# SimonSays.net
KiCad netlist of a schematic drawn in Altium Designer
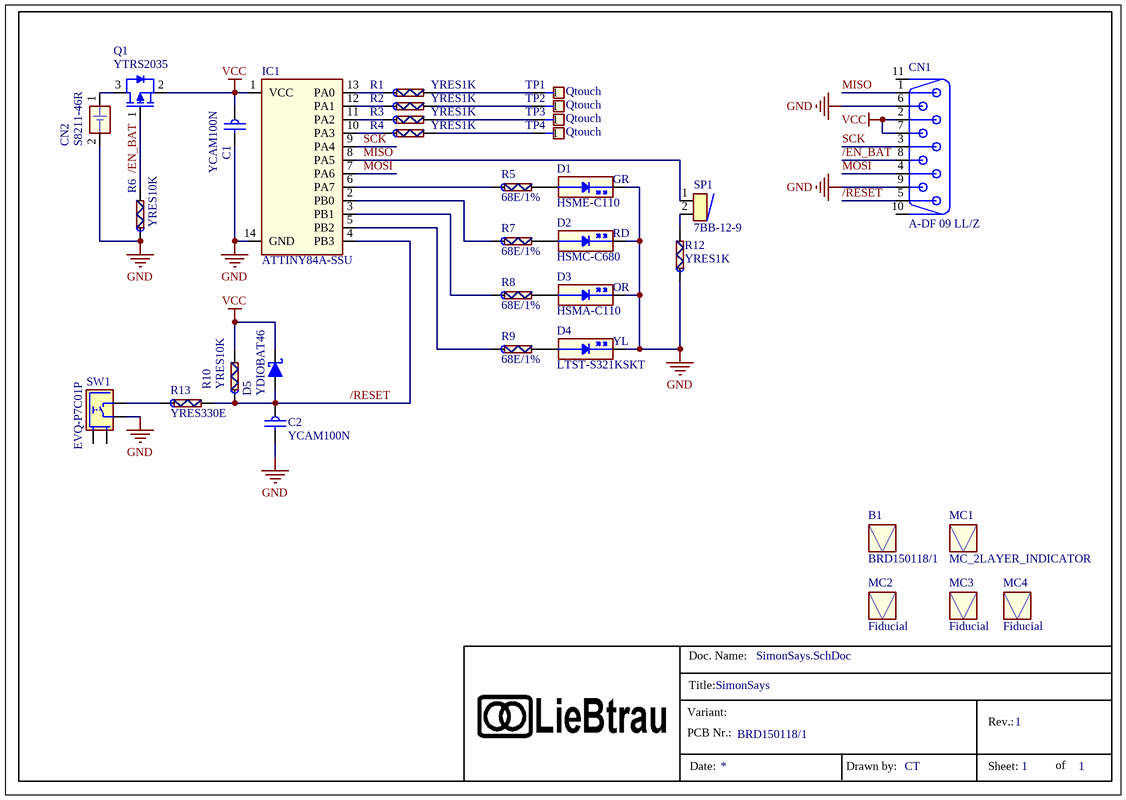
[diagram p0: SimonSays.SchDoc]

(export (version "E")
  (design (tool "Eeschema 10.0.6"))
  (components
    (comp (ref "B1") (value "~") (footprint "MC_BoardNr") (libsource (lib "Testing") (part "BD_PCB")))
    (comp (ref "C1")
      (value "YCAM100N")
      (footprint "CA_STD1206_H16")
      (description "100N")
      (libsource (lib "Testing") (part "CA_STD_NonPolar"))
    )
    (comp (ref "C2")
      (value "YCAM100N")
      (footprint "CA_STD1206_H16")
      (description "100N")
      (libsource (lib "Testing") (part "CA_STD_NonPolar"))
    )
    (comp (ref "CN1")
      (value "A-DF 09 LL/Z")
      (footprint "CN_SUBD_9P_FEMALE_EDGE")
      (description "Edge mount Connector")
      (libsource (lib "Diverse") (part "CN_DB9 FEM"))
    )
    (comp (ref "CN2")
      (value "S8211-46R")
      (footprint "CN_BAT_CLIP_HARWIN_S8211-46R")
      (description "Coin cell holder CR2032")
      (libsource (lib "Diverse") (part "CN_BAT_CLIP_1"))
    )
    (comp (ref "D1")
      (value "HSME-C110")
      (footprint "DI_AVAGO_HSMx-C680")
      (description "GREEN")
      (libsource (lib "Diverse") (part "DI_STD_LED"))
    )
    (comp (ref "D2")
      (value "HSMC-C680")
      (footprint "DI_AVAGO_HSMx-C680")
      (description "RED")
      (libsource (lib "") (part "DI_STD_LED_1"))
    )
    (comp (ref "D3")
      (value "HSMA-C110")
      (footprint "DI_AVAGO_HSMx-C680")
      (description "AMBER")
      (libsource (lib "") (part "DI_STD_LED_1"))
    )
    (comp (ref "D4")
      (value "LTST-S321KSKT")
      (footprint "DI_AVAGO_HSMx-C680")
      (description "YELLOW")
      (libsource (lib "") (part "DI_STD_LED_1"))
    )
    (comp (ref "D5")
      (value "YDIOBAT46")
      (footprint "DI_SOD123")
      (description "BAT46")
      (libsource (lib "Testing") (part "DI_STD_Schottky"))
    )
    (comp (ref "IC1")
      (value "ATTINY84A-SSU")
      (footprint "SC_SO14")
      (libsource (lib "Diverse") (part "IC_ATMEL_ATTINY84A"))
    )
    (comp (ref "MC1")
      (value "MC_2LAYER_INDICATOR")
      (footprint "MC_2LAYER_INDICATOR")
      (libsource (lib "Testing") (part "MC_MechPart_No_BOM"))
    )
    (comp (ref "MC2")
      (value "Fiducial")
      (footprint "MC_FIDUCIAL")
      (libsource (lib "Testing") (part "MC_MechPart_No_BOM"))
    )
    (comp (ref "MC3")
      (value "Fiducial")
      (footprint "MC_FIDUCIAL")
      (libsource (lib "Testing") (part "MC_MechPart_No_BOM"))
    )
    (comp (ref "MC4")
      (value "Fiducial")
      (footprint "MC_FIDUCIAL")
      (libsource (lib "Testing") (part "MC_MechPart_No_BOM"))
    )
    (comp (ref "Q1")
      (value "YTRS2035")
      (footprint "SC_SOT23_3P")
      (description "DMP2035")
      (libsource (lib "Testing") (part "TR_STD_FETP_ENH_GDS132"))
    )
    (comp (ref "R1")
      (value "YRES1K")
      (footprint "RE_STD1206_H6")
      (description "1K")
      (libsource (lib "") (part "RE_STD_Resistor_1"))
    )
    (comp (ref "R2")
      (value "YRES1K")
      (footprint "RE_STD1206_H6")
      (description "1K")
      (libsource (lib "") (part "RE_STD_Resistor_1"))
    )
    (comp (ref "R3")
      (value "YRES1K")
      (footprint "RE_STD1206_H6")
      (description "1K")
      (libsource (lib "") (part "RE_STD_Resistor_1"))
    )
    (comp (ref "R4")
      (value "YRES1K")
      (footprint "RE_STD1206_H6")
      (description "1K")
      (libsource (lib "") (part "RE_STD_Resistor_1"))
    )
    (comp (ref "R5")
      (value "68E/1%")
      (footprint "RE_STD1206_H6")
      (description "68E")
      (libsource (lib "") (part "RE_STD_Resistor_1"))
    )
    (comp (ref "R6")
      (value "YRES10K")
      (footprint "RE_STD1206_H6")
      (description "10K")
      (libsource (lib "Testing") (part "RE_STD_Resistor"))
    )
    (comp (ref "R7")
      (value "68E/1%")
      (footprint "RE_STD1206_H6")
      (description "68E")
      (libsource (lib "") (part "RE_STD_Resistor_1"))
    )
    (comp (ref "R8")
      (value "68E/1%")
      (footprint "RE_STD1206_H6")
      (description "68E")
      (libsource (lib "") (part "RE_STD_Resistor_1"))
    )
    (comp (ref "R9")
      (value "68E/1%")
      (footprint "RE_STD1206_H6")
      (description "68E")
      (libsource (lib "") (part "RE_STD_Resistor_1"))
    )
    (comp (ref "R10")
      (value "YRES10K")
      (footprint "RE_STD1206_H6")
      (description "10K")
      (libsource (lib "Testing") (part "RE_STD_Resistor"))
    )
    (comp (ref "R12")
      (value "YRES1K")
      (footprint "RE_STD1206_H6")
      (description "1K")
      (libsource (lib "Testing") (part "RE_STD_Resistor"))
    )
    (comp (ref "R13")
      (value "YRES330E")
      (footprint "RE_STD1206_H6")
      (description "330E")
      (libsource (lib "") (part "RE_STD_Resistor_1"))
    )
    (comp (ref "SP1")
      (value "7BB-12-9")
      (footprint "LS_MURATA_7BB-12-9")
      (description "12mm piezo")
      (libsource (lib "Diverse") (part "SP_PIEZO"))
    )
    (comp (ref "SW1")
      (value "EVQ-P7C01P")
      (footprint "CN_PANASONIC_EVQ-P7")
      (libsource (lib "Diverse") (part "SW_Tactile_90D_SPST_NO"))
    )
    (comp (ref "TP1")
      (value "Qtouch")
      (footprint "SW_ATMEL_QTOUCH_BUTTON")
      (libsource (lib "Diverse") (part "CN_TP_1mm3"))
    )
    (comp (ref "TP2")
      (value "Qtouch")
      (footprint "SW_ATMEL_QTOUCH_BUTTON")
      (libsource (lib "Diverse") (part "CN_TP_1mm3"))
    )
    (comp (ref "TP3")
      (value "Qtouch")
      (footprint "SW_ATMEL_QTOUCH_BUTTON")
      (libsource (lib "Diverse") (part "CN_TP_1mm3"))
    )
    (comp (ref "TP4")
      (value "Qtouch")
      (footprint "SW_ATMEL_QTOUCH_BUTTON")
      (libsource (lib "Diverse") (part "CN_TP_1mm3"))
    )
  )
  (nets
    (net (code "1") (name "/MISO") (class "Default")
      (node (ref "CN1") (pin "1") (pinfunction "1_1") (pintype "passive"))
      (node (ref "IC1") (pin "8") (pinfunction "PA5_8") (pintype "passive"))
      (node (ref "SP1") (pin "1") (pintype "passive"))
    )
    (net (code "2") (name "/MOSI") (class "Default")
      (node (ref "CN1") (pin "4") (pinfunction "4_4") (pintype "passive"))
      (node (ref "IC1") (pin "7") (pinfunction "PA6_7") (pintype "passive"))
    )
    (net (code "3") (name "/SCK") (class "Default")
      (node (ref "CN1") (pin "3") (pinfunction "3_3") (pintype "passive"))
      (node (ref "IC1") (pin "9") (pinfunction "PA4_9") (pintype "passive"))
    )
    (net (code "4") (name "/{slash}EN_BAT") (class "Default")
      (node (ref "CN1") (pin "8") (pinfunction "8_8") (pintype "passive"))
      (node (ref "Q1") (pin "1") (pinfunction "G_1") (pintype "passive"))
      (node (ref "R6") (pin "2") (pinfunction "2_2") (pintype "passive"))
    )
    (net (code "5") (name "/{slash}RESET") (class "Default")
      (node (ref "C2") (pin "1") (pinfunction "1_1") (pintype "passive"))
      (node (ref "CN1") (pin "5") (pinfunction "5_5") (pintype "passive"))
      (node (ref "D5") (pin "A") (pinfunction "A_A") (pintype "passive"))
      (node (ref "IC1") (pin "4") (pinfunction "PB3_4") (pintype "passive"))
      (node (ref "R10") (pin "1") (pinfunction "1_1") (pintype "passive"))
      (node (ref "R13") (pin "2") (pinfunction "2_2") (pintype "passive"))
    )
    (net (code "6") (name "GND") (class "Default")
      (node (ref "C1") (pin "2") (pinfunction "2_2") (pintype "passive"))
      (node (ref "C2") (pin "2") (pinfunction "2_2") (pintype "passive"))
      (node (ref "CN1") (pin "6") (pinfunction "6_6") (pintype "passive"))
      (node (ref "CN1") (pin "9") (pinfunction "9_9") (pintype "passive"))
      (node (ref "CN2") (pin "2") (pinfunction "2_2") (pintype "passive"))
      (node (ref "D1") (pin "C") (pinfunction "C_C") (pintype "passive"))
      (node (ref "D2") (pin "C") (pinfunction "C_C") (pintype "passive"))
      (node (ref "D3") (pin "C") (pinfunction "C_C") (pintype "passive"))
      (node (ref "D4") (pin "C") (pinfunction "C_C") (pintype "passive"))
      (node (ref "IC1") (pin "14") (pinfunction "GND_14") (pintype "passive"))
      (node (ref "R12") (pin "1") (pinfunction "1_1") (pintype "passive"))
      (node (ref "R6") (pin "1") (pinfunction "1_1") (pintype "passive"))
      (node (ref "SW1") (pin "2") (pinfunction "2_2") (pintype "passive"))
    )
    (net (code "7") (name "Net-(D1-PadA)") (class "Default")
      (node (ref "D1") (pin "A") (pinfunction "A_A") (pintype "passive"))
      (node (ref "R5") (pin "2") (pinfunction "2_2") (pintype "passive"))
    )
    (net (code "8") (name "Net-(D2-PadA)") (class "Default")
      (node (ref "D2") (pin "A") (pinfunction "A_A") (pintype "passive"))
      (node (ref "R7") (pin "2") (pinfunction "2_2") (pintype "passive"))
    )
    (net (code "9") (name "Net-(D3-PadA)") (class "Default")
      (node (ref "D3") (pin "A") (pinfunction "A_A") (pintype "passive"))
      (node (ref "R8") (pin "2") (pinfunction "2_2") (pintype "passive"))
    )
    (net (code "10") (name "Net-(D4-PadA)") (class "Default")
      (node (ref "D4") (pin "A") (pinfunction "A_A") (pintype "passive"))
      (node (ref "R9") (pin "2") (pinfunction "2_2") (pintype "passive"))
    )
    (net (code "11") (name "Net-(IC1-PA0)") (class "Default")
      (node (ref "IC1") (pin "13") (pinfunction "PA0_13") (pintype "passive"))
      (node (ref "R1") (pin "1") (pinfunction "1_1") (pintype "passive"))
    )
    (net (code "12") (name "Net-(IC1-PA1)") (class "Default")
      (node (ref "IC1") (pin "12") (pinfunction "PA1_12") (pintype "passive"))
      (node (ref "R2") (pin "1") (pinfunction "1_1") (pintype "passive"))
    )
    (net (code "13") (name "Net-(IC1-PA2)") (class "Default")
      (node (ref "IC1") (pin "11") (pinfunction "PA2_11") (pintype "passive"))
      (node (ref "R3") (pin "1") (pinfunction "1_1") (pintype "passive"))
    )
    (net (code "14") (name "Net-(IC1-PA3)") (class "Default")
      (node (ref "IC1") (pin "10") (pinfunction "PA3_10") (pintype "passive"))
      (node (ref "R4") (pin "1") (pinfunction "1_1") (pintype "passive"))
    )
    (net (code "15") (name "Net-(IC1-PA7)") (class "Default")
      (node (ref "IC1") (pin "6") (pinfunction "PA7_6") (pintype "passive"))
      (node (ref "R5") (pin "1") (pinfunction "1_1") (pintype "passive"))
    )
    (net (code "16") (name "Net-(IC1-PB0)") (class "Default")
      (node (ref "IC1") (pin "2") (pinfunction "PB0_2") (pintype "passive"))
      (node (ref "R7") (pin "1") (pinfunction "1_1") (pintype "passive"))
    )
    (net (code "17") (name "Net-(IC1-PB1)") (class "Default")
      (node (ref "IC1") (pin "3") (pinfunction "PB1_3") (pintype "passive"))
      (node (ref "R8") (pin "1") (pinfunction "1_1") (pintype "passive"))
    )
    (net (code "18") (name "Net-(IC1-PB2)") (class "Default")
      (node (ref "IC1") (pin "5") (pinfunction "PB2_5") (pintype "passive"))
      (node (ref "R9") (pin "1") (pinfunction "1_1") (pintype "passive"))
    )
    (net (code "19") (name "Net-(Q1-D)") (class "Default")
      (node (ref "CN2") (pin "1") (pintype "passive"))
      (node (ref "Q1") (pin "3") (pinfunction "D_3") (pintype "passive"))
    )
    (net (code "20") (name "Net-(R1-Pad2)") (class "Default")
      (node (ref "R1") (pin "2") (pinfunction "2_2") (pintype "passive"))
      (node (ref "TP1") (pin "1") (pinfunction "1_1") (pintype "passive"))
    )
    (net (code "21") (name "Net-(R2-Pad2)") (class "Default")
      (node (ref "R2") (pin "2") (pinfunction "2_2") (pintype "passive"))
      (node (ref "TP2") (pin "1") (pinfunction "1_1") (pintype "passive"))
    )
    (net (code "22") (name "Net-(R3-Pad2)") (class "Default")
      (node (ref "R3") (pin "2") (pinfunction "2_2") (pintype "passive"))
      (node (ref "TP3") (pin "1") (pinfunction "1_1") (pintype "passive"))
    )
    (net (code "23") (name "Net-(R4-Pad2)") (class "Default")
      (node (ref "R4") (pin "2") (pinfunction "2_2") (pintype "passive"))
      (node (ref "TP4") (pin "1") (pinfunction "1_1") (pintype "passive"))
    )
    (net (code "24") (name "Net-(R12-Pad2)") (class "Default")
      (node (ref "R12") (pin "2") (pinfunction "2_2") (pintype "passive"))
      (node (ref "SP1") (pin "2") (pintype "passive"))
    )
    (net (code "25") (name "Net-(R13-Pad1)") (class "Default")
      (node (ref "R13") (pin "1") (pinfunction "1_1") (pintype "passive"))
      (node (ref "SW1") (pin "1") (pinfunction "1_1") (pintype "passive"))
    )
    (net (code "26") (name "VCC") (class "Default")
      (node (ref "C1") (pin "1") (pinfunction "1_1") (pintype "passive"))
      (node (ref "CN1") (pin "2") (pinfunction "2_2") (pintype "passive"))
      (node (ref "CN1") (pin "7") (pinfunction "7_7") (pintype "passive"))
      (node (ref "D5") (pin "C") (pinfunction "C_C") (pintype "passive"))
      (node (ref "IC1") (pin "1") (pinfunction "VCC_1") (pintype "passive"))
      (node (ref "Q1") (pin "2") (pinfunction "S_2") (pintype "passive"))
      (node (ref "R10") (pin "2") (pinfunction "2_2") (pintype "passive"))
    )
    (net (code "27") (name "unconnected-(CN1-Pad10)") (class "Default")
      (node (ref "CN1") (pin "10") (pinfunction "10_10") (pintype "passive"))
    )
    (net (code "28") (name "unconnected-(CN1-Pad11)") (class "Default")
      (node (ref "CN1") (pin "11") (pinfunction "11_11") (pintype "passive"))
    )
    (net (code "29") (name "unconnected-(SW1-PadSH1)") (class "Default")
      (node (ref "SW1") (pin "SH1") (pinfunction "SH1_SH1") (pintype "passive"))
    )
    (net (code "30") (name "unconnected-(SW1-PadSH2)") (class "Default")
      (node (ref "SW1") (pin "SH2") (pinfunction "SH2_SH2") (pintype "passive"))
    )
  )
)
